# Ampli_audio.net
KiCad netlist of a schematic drawn in Altium Designer
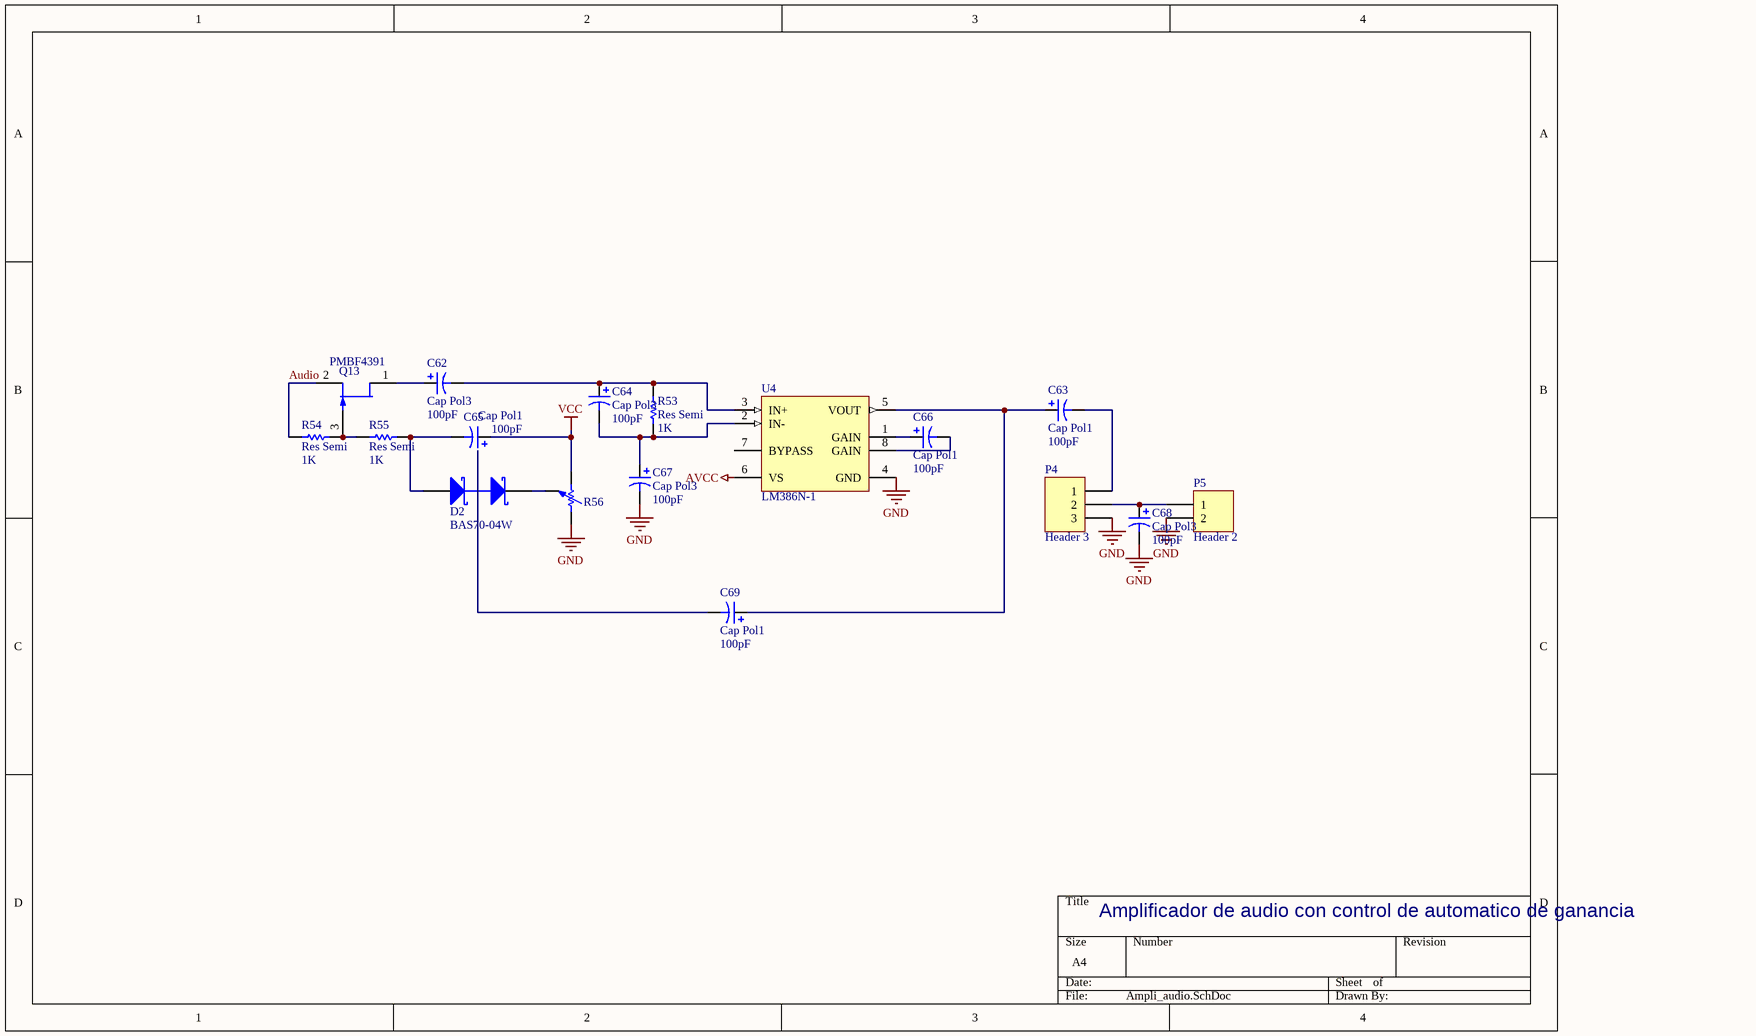
[diagram p0: Ampli_audio.SchDoc]

(export (version "E")
  (design (tool "Eeschema 10.0.6"))
  (components
    (comp (ref "C62")
      (value "Cap Pol3")
      (footprint "C0805")
      (description "Polarized Capacitor (Surface Mount)")
      (fields (field (name "ALTIUM_VALUE") "100pF") (field (name "PUBLISHER") "Altium Limited"))
      (libsource (lib "Miscellaneous Devices") (part "Cap Pol3"))
    )
    (comp (ref "C63")
      (value "Cap Pol1")
      (footprint "B")
      (description "Polarized Capacitor (Radial)")
      (fields (field (name "ALTIUM_VALUE") "100pF") (field (name "PUBLISHER") "Altium Limited"))
      (libsource (lib "Miscellaneous Devices") (part "Cap Pol1"))
    )
    (comp (ref "C64")
      (value "Cap Pol3")
      (footprint "C0805")
      (description "Polarized Capacitor (Surface Mount)")
      (fields (field (name "ALTIUM_VALUE") "100pF") (field (name "PUBLISHER") "Altium Limited"))
      (libsource (lib "Miscellaneous Devices") (part "Cap Pol3"))
    )
    (comp (ref "C65")
      (value "Cap Pol1")
      (footprint "B")
      (description "Polarized Capacitor (Radial)")
      (fields (field (name "ALTIUM_VALUE") "100pF") (field (name "PUBLISHER") "Altium Limited"))
      (libsource (lib "Miscellaneous Devices") (part "Cap Pol1"))
    )
    (comp (ref "C66")
      (value "Cap Pol1")
      (footprint "B")
      (description "Polarized Capacitor (Radial)")
      (fields (field (name "ALTIUM_VALUE") "100pF") (field (name "PUBLISHER") "Altium Limited"))
      (libsource (lib "Miscellaneous Devices") (part "Cap Pol1"))
    )
    (comp (ref "C67")
      (value "Cap Pol3")
      (footprint "C0805")
      (description "Polarized Capacitor (Surface Mount)")
      (fields (field (name "ALTIUM_VALUE") "100pF") (field (name "PUBLISHER") "Altium Limited"))
      (libsource (lib "Miscellaneous Devices") (part "Cap Pol3"))
    )
    (comp (ref "C68")
      (value "Cap Pol3")
      (footprint "C0805")
      (description "Polarized Capacitor (Surface Mount)")
      (fields (field (name "ALTIUM_VALUE") "100pF") (field (name "PUBLISHER") "Altium Limited"))
      (libsource (lib "Miscellaneous Devices") (part "Cap Pol3"))
    )
    (comp (ref "C69")
      (value "Cap Pol1")
      (footprint "B")
      (description "Polarized Capacitor (Radial)")
      (fields (field (name "ALTIUM_VALUE") "100pF") (field (name "PUBLISHER") "Altium Limited"))
      (libsource (lib "Miscellaneous Devices") (part "Cap Pol1"))
    )
    (comp (ref "D2")
      (value "BAS70-04W")
      (footprint "SOT323_N")
      (description "Schottky Barrier Double Diode")
      (fields (field (name "PUBLISHER") "Altium Limited"))
      (libsource (lib "Philips Discrete Diode - Schottky") (part "BAS70-04W"))
    )
    (comp (ref "P4")
      (value "Header 3")
      (footprint "HDR1X3")
      (description "Header, 3-Pin")
      (fields (field (name "PUBLISHER") "Altium Limited"))
      (libsource (lib "Miscellaneous Connectors") (part "Header 3"))
    )
    (comp (ref "P5")
      (value "Header 2")
      (footprint "HDR1X2")
      (description "Header, 2-Pin")
      (fields (field (name "PUBLISHER") "Altium Limited"))
      (libsource (lib "Miscellaneous Connectors") (part "Header 2"))
    )
    (comp (ref "Q13")
      (value "PMBF4391")
      (footprint "SOT-23")
      (description "N-channel Silicon Junction Field-effect Transistor")
      (fields (field (name "PUBLISHER") "Altium Limited"))
      (libsource (lib "Philips Discrete JFET") (part "PMBF4391"))
    )
    (comp (ref "R53")
      (value "Res Semi")
      (footprint "2012[0805]")
      (description "Semiconductor Resistor")
      (fields (field (name "ALTIUM_VALUE") "1K") (field (name "PUBLISHER") "Altium Limited"))
      (libsource (lib "Miscellaneous Devices") (part "Res Semi"))
    )
    (comp (ref "R54")
      (value "Res Semi")
      (footprint "2012[0805]")
      (description "Semiconductor Resistor")
      (fields (field (name "ALTIUM_VALUE") "1K") (field (name "PUBLISHER") "Altium Limited"))
      (libsource (lib "Miscellaneous Devices") (part "Res Semi"))
    )
    (comp (ref "R55")
      (value "Res Semi")
      (footprint "2012[0805]")
      (description "Semiconductor Resistor")
      (fields (field (name "ALTIUM_VALUE") "1K") (field (name "PUBLISHER") "Altium Limited"))
      (libsource (lib "Miscellaneous Devices") (part "Res Semi"))
    )
    (comp (ref "R56") (value "Pot") (footprint "Potenciometro") (libsource (lib "epf") (part "Pot")))
    (comp (ref "U4")
      (value "LM386N-1")
      (footprint "DIP8")
      (description "Low Voltage Audio Power Amplifier")
      (fields
        (field (name "MANUFACTURER") "National Semiconductor")
        (field (name "DIGIKEYPARTNUMBER") "LM386N-1-ND")
      )
      (libsource (lib "NSC Audio") (part "LM386N-1"))
    )
  )
  (nets
    (net (code "1") (name "/Audio") (class "Default")
      (node (ref "Q13") (pin "2") (pinfunction "S_2") (pintype "passive"))
      (node (ref "R54") (pin "1") (pinfunction "1_1") (pintype "passive"))
    )
    (net (code "2") (name "AVCC") (class "Default")
      (node (ref "U4") (pin "6") (pinfunction "VS_6") (pintype "power_in"))
    )
    (net (code "3") (name "GND") (class "Default")
      (node (ref "C67") (pin "2") (pinfunction "2_2") (pintype "passive"))
      (node (ref "C68") (pin "2") (pinfunction "2_2") (pintype "passive"))
      (node (ref "P4") (pin "3") (pinfunction "3_3") (pintype "passive"))
      (node (ref "P5") (pin "2") (pinfunction "2_2") (pintype "passive"))
      (node (ref "R56") (pin "1") (pinfunction "1_1") (pintype "passive"))
      (node (ref "U4") (pin "4") (pinfunction "GND_4") (pintype "power_in"))
    )
    (net (code "4") (name "Net-(C63-Pad2)") (class "Default")
      (node (ref "C63") (pin "2") (pinfunction "2_2") (pintype "passive"))
      (node (ref "P4") (pin "1") (pinfunction "1_1") (pintype "passive"))
    )
    (net (code "5") (name "Net-(C66-Pad1)") (class "Default")
      (node (ref "C66") (pin "1") (pinfunction "1_1") (pintype "passive"))
      (node (ref "U4") (pin "1") (pinfunction "GAIN_1") (pintype "passive"))
    )
    (net (code "6") (name "Net-(C66-Pad2)") (class "Default")
      (node (ref "C66") (pin "2") (pinfunction "2_2") (pintype "passive"))
      (node (ref "U4") (pin "8") (pinfunction "GAIN_8") (pintype "passive"))
    )
    (net (code "7") (name "Net-(C68-Pad1)") (class "Default")
      (node (ref "C68") (pin "1") (pinfunction "1_1") (pintype "passive"))
      (node (ref "P4") (pin "2") (pinfunction "2_2") (pintype "passive"))
      (node (ref "P5") (pin "1") (pinfunction "1_1") (pintype "passive"))
    )
    (net (code "8") (name "Net-(D2-A)") (class "Default")
      (node (ref "C65") (pin "2") (pinfunction "2_2") (pintype "passive"))
      (node (ref "D2") (pin "1") (pinfunction "A_1") (pintype "passive"))
      (node (ref "R55") (pin "2") (pinfunction "2_2") (pintype "passive"))
    )
    (net (code "9") (name "Net-(D2-C)") (class "Default")
      (node (ref "C69") (pin "2") (pinfunction "2_2") (pintype "passive"))
      (node (ref "D2") (pin "3") (pinfunction "C_3") (pintype "passive"))
    )
    (net (code "10") (name "Net-(D2-K)") (class "Default")
      (node (ref "D2") (pin "2") (pinfunction "K_2") (pintype "passive"))
      (node (ref "R56") (pin "3") (pinfunction "3_3") (pintype "passive"))
    )
    (net (code "11") (name "Net-(Q13-D)") (class "Default")
      (node (ref "C62") (pin "1") (pinfunction "1_1") (pintype "passive"))
      (node (ref "Q13") (pin "1") (pinfunction "D_1") (pintype "passive"))
    )
    (net (code "12") (name "Net-(Q13-G)") (class "Default")
      (node (ref "Q13") (pin "3") (pinfunction "G_3") (pintype "passive"))
      (node (ref "R54") (pin "2") (pinfunction "2_2") (pintype "passive"))
      (node (ref "R55") (pin "1") (pinfunction "1_1") (pintype "passive"))
    )
    (net (code "13") (name "Net-(U4-IN+)") (class "Default")
      (node (ref "C62") (pin "2") (pinfunction "2_2") (pintype "passive"))
      (node (ref "C64") (pin "1") (pinfunction "1_1") (pintype "passive"))
      (node (ref "R53") (pin "2") (pinfunction "2_2") (pintype "passive"))
      (node (ref "U4") (pin "3") (pinfunction "IN+_3") (pintype "input"))
    )
    (net (code "14") (name "Net-(U4-IN-)") (class "Default")
      (node (ref "C64") (pin "2") (pinfunction "2_2") (pintype "passive"))
      (node (ref "C67") (pin "1") (pinfunction "1_1") (pintype "passive"))
      (node (ref "R53") (pin "1") (pinfunction "1_1") (pintype "passive"))
      (node (ref "U4") (pin "2") (pinfunction "IN-_2") (pintype "input"))
    )
    (net (code "15") (name "Net-(U4-VOUT)") (class "Default")
      (node (ref "C63") (pin "1") (pinfunction "1_1") (pintype "passive"))
      (node (ref "C69") (pin "1") (pinfunction "1_1") (pintype "passive"))
      (node (ref "U4") (pin "5") (pinfunction "VOUT_5") (pintype "output"))
    )
    (net (code "16") (name "VCC") (class "Default")
      (node (ref "C65") (pin "1") (pinfunction "1_1") (pintype "passive"))
      (node (ref "R56") (pin "2") (pinfunction "2_2") (pintype "passive"))
    )
    (net (code "17") (name "unconnected-(U4-BYPASS-Pad7)") (class "Default")
      (node (ref "U4") (pin "7") (pinfunction "BYPASS_7") (pintype "passive"))
    )
  )
)
